# energy_harvesting.net
KiCad netlist of a schematic drawn in Altium Designer
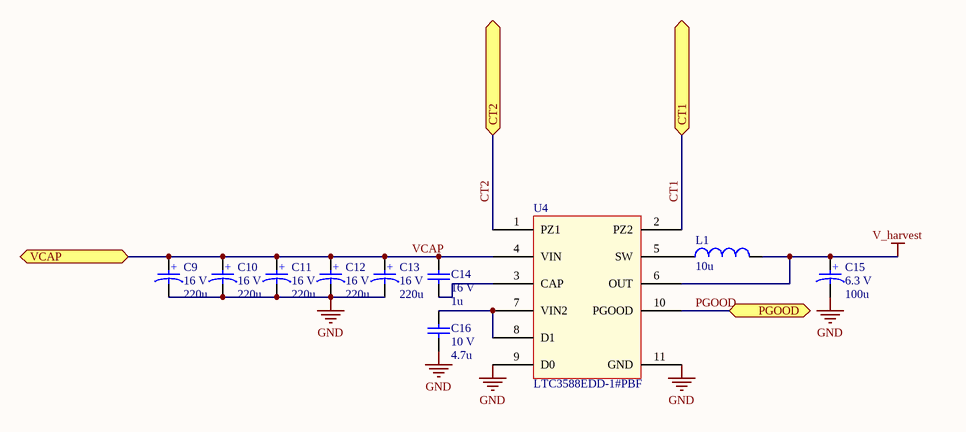
[diagram p0: energy_harvesting.SchDoc]

(export (version "E")
  (design (tool "Eeschema 10.0.6"))
  (components
    (comp (ref "C9")
      (value "220u")
      (footprint "2917")
      (description "220µF ±10% Molded Tantalum Capacitors 16V")
      (fields
        (field (name "TOLERANCE") "10%")
        (field (name "VOLTAGE RATED") "16 V")
        (field (name "MANUFACTURER PART NUMBER") "T495X227K016ATE100")
      )
      (libsource (lib "capacitors") (part "T495X227K016ATE100"))
    )
    (comp (ref "C10")
      (value "220u")
      (footprint "2917")
      (description "220µF ±10% Molded Tantalum Capacitors 16V")
      (fields
        (field (name "TOLERANCE") "10%")
        (field (name "VOLTAGE RATED") "16 V")
        (field (name "MANUFACTURER PART NUMBER") "T495X227K016ATE100")
      )
      (libsource (lib "capacitors") (part "T495X227K016ATE100"))
    )
    (comp (ref "C11")
      (value "220u")
      (footprint "2917")
      (description "220µF ±10% Molded Tantalum Capacitors 16V")
      (fields
        (field (name "TOLERANCE") "10%")
        (field (name "VOLTAGE RATED") "16 V")
        (field (name "MANUFACTURER PART NUMBER") "T495X227K016ATE100")
      )
      (libsource (lib "capacitors") (part "T495X227K016ATE100"))
    )
    (comp (ref "C12")
      (value "220u")
      (footprint "2917")
      (description "220µF ±10% Molded Tantalum Capacitors 16V")
      (fields
        (field (name "TOLERANCE") "10%")
        (field (name "VOLTAGE RATED") "16 V")
        (field (name "MANUFACTURER PART NUMBER") "T495X227K016ATE100")
      )
      (libsource (lib "capacitors") (part "T495X227K016ATE100"))
    )
    (comp (ref "C13")
      (value "220u")
      (footprint "2917")
      (description "220µF ±10% Molded Tantalum Capacitors 16V")
      (fields
        (field (name "TOLERANCE") "10%")
        (field (name "VOLTAGE RATED") "16 V")
        (field (name "MANUFACTURER PART NUMBER") "T495X227K016ATE100")
      )
      (libsource (lib "capacitors") (part "T495X227K016ATE100"))
    )
    (comp (ref "C14")
      (value "1u")
      (footprint "0603")
      (description "1µF ±10% 16V Ceramic Capacitor X7R 0603")
      (fields
        (field (name "VOLTAGE RATED") "16 V")
        (field (name "TOLERANCE") "10%")
        (field (name "MANUFACTURER PART NUMBER") "C1608X7R1C105K080AC")
      )
      (libsource (lib "capacitors") (part "C1608X7R1C105K080AC"))
    )
    (comp (ref "C15")
      (value "100u")
      (footprint "1206 - POLAR MARKING")
      (description "100µF ±20% Molded Tantalum Capacitors 6.3V 1206")
      (fields
        (field (name "VOLTAGE RATED") "6.3 V")
        (field (name "TOLERANCE") "20%")
        (field (name "MANUFACTURER PART NUMBER") "F930J107MAA")
      )
      (libsource (lib "capacitors") (part "F930J107MAA"))
    )
    (comp (ref "C16")
      (value "4.7u")
      (footprint "0603")
      (description "4.7µF ±10% 10V Ceramic Capacitor X5R 0603")
      (fields
        (field (name "TOLERANCE") "10%")
        (field (name "VOLTAGE RATED") "10 V")
        (field (name "MANUFACTURER PART NUMBER") "CGB3B1X5R1A475K055AC")
      )
      (libsource (lib "capacitors") (part "CGB3B1X5R1A475K055AC"))
    )
    (comp (ref "L1")
      (value "10u")
      (footprint "CDRH2D18")
      (description "10µH Shielded Inductor 1A 180 mOhm Max Nonstandard")
      (fields
        (field (name "TOLERANCE") "30%")
        (field (name "MANUFACTURER PART NUMBER") "CDRH2D18/LDNP-100NC")
      )
      (libsource (lib "inductors") (part "CDRH2D18/LDNP-100NC"))
    )
    (comp (ref "U4")
      (value "LTC3588EDD-1#PBF")
      (footprint "QFN-10")
      (description "Piezoelectric Energy Harvesting Power Supply")
      (libsource (lib "voltage regulator") (part "LTC3588EDD-1#PBF"))
    )
  )
  (nets
    (net (code "1") (name "/CT1") (class "Default")
      (node (ref "U4") (pin "2") (pinfunction "PZ2_2") (pintype "passive"))
    )
    (net (code "2") (name "/CT2") (class "Default")
      (node (ref "U4") (pin "1") (pinfunction "PZ1_1") (pintype "passive"))
    )
    (net (code "3") (name "/PGOOD") (class "Default")
      (node (ref "U4") (pin "10") (pinfunction "PGOOD_10") (pintype "passive"))
    )
    (net (code "4") (name "/VCAP") (class "Default")
      (node (ref "C10") (pin "1") (pintype "passive"))
      (node (ref "C11") (pin "1") (pintype "passive"))
      (node (ref "C12") (pin "1") (pintype "passive"))
      (node (ref "C13") (pin "1") (pintype "passive"))
      (node (ref "C14") (pin "1") (pintype "passive"))
      (node (ref "C9") (pin "1") (pintype "passive"))
      (node (ref "U4") (pin "4") (pinfunction "VIN_4") (pintype "passive"))
    )
    (net (code "5") (name "GND") (class "Default")
      (node (ref "C10") (pin "2") (pintype "passive"))
      (node (ref "C11") (pin "2") (pintype "passive"))
      (node (ref "C12") (pin "2") (pintype "passive"))
      (node (ref "C13") (pin "2") (pintype "passive"))
      (node (ref "C15") (pin "2") (pintype "passive"))
      (node (ref "C16") (pin "2") (pintype "passive"))
      (node (ref "C9") (pin "2") (pintype "passive"))
      (node (ref "U4") (pin "11") (pinfunction "GND_11") (pintype "passive"))
      (node (ref "U4") (pin "9") (pinfunction "D0_9") (pintype "passive"))
    )
    (net (code "6") (name "Net-(U4-CAP)") (class "Default")
      (node (ref "C14") (pin "2") (pintype "passive"))
      (node (ref "U4") (pin "3") (pinfunction "CAP_3") (pintype "passive"))
    )
    (net (code "7") (name "Net-(U4-D1)") (class "Default")
      (node (ref "C16") (pin "1") (pintype "passive"))
      (node (ref "U4") (pin "7") (pinfunction "VIN2_7") (pintype "passive"))
      (node (ref "U4") (pin "8") (pinfunction "D1_8") (pintype "passive"))
    )
    (net (code "8") (name "Net-(U4-SW)") (class "Default")
      (node (ref "L1") (pin "2") (pintype "passive"))
      (node (ref "U4") (pin "5") (pinfunction "SW_5") (pintype "passive"))
    )
    (net (code "9") (name "V_harvest") (class "Default")
      (node (ref "C15") (pin "1") (pintype "passive"))
      (node (ref "L1") (pin "1") (pintype "passive"))
      (node (ref "U4") (pin "6") (pinfunction "OUT_6") (pintype "passive"))
    )
  )
)
